# ConsoleSchematic.net
KiCad netlist of a schematic drawn in EAGLE
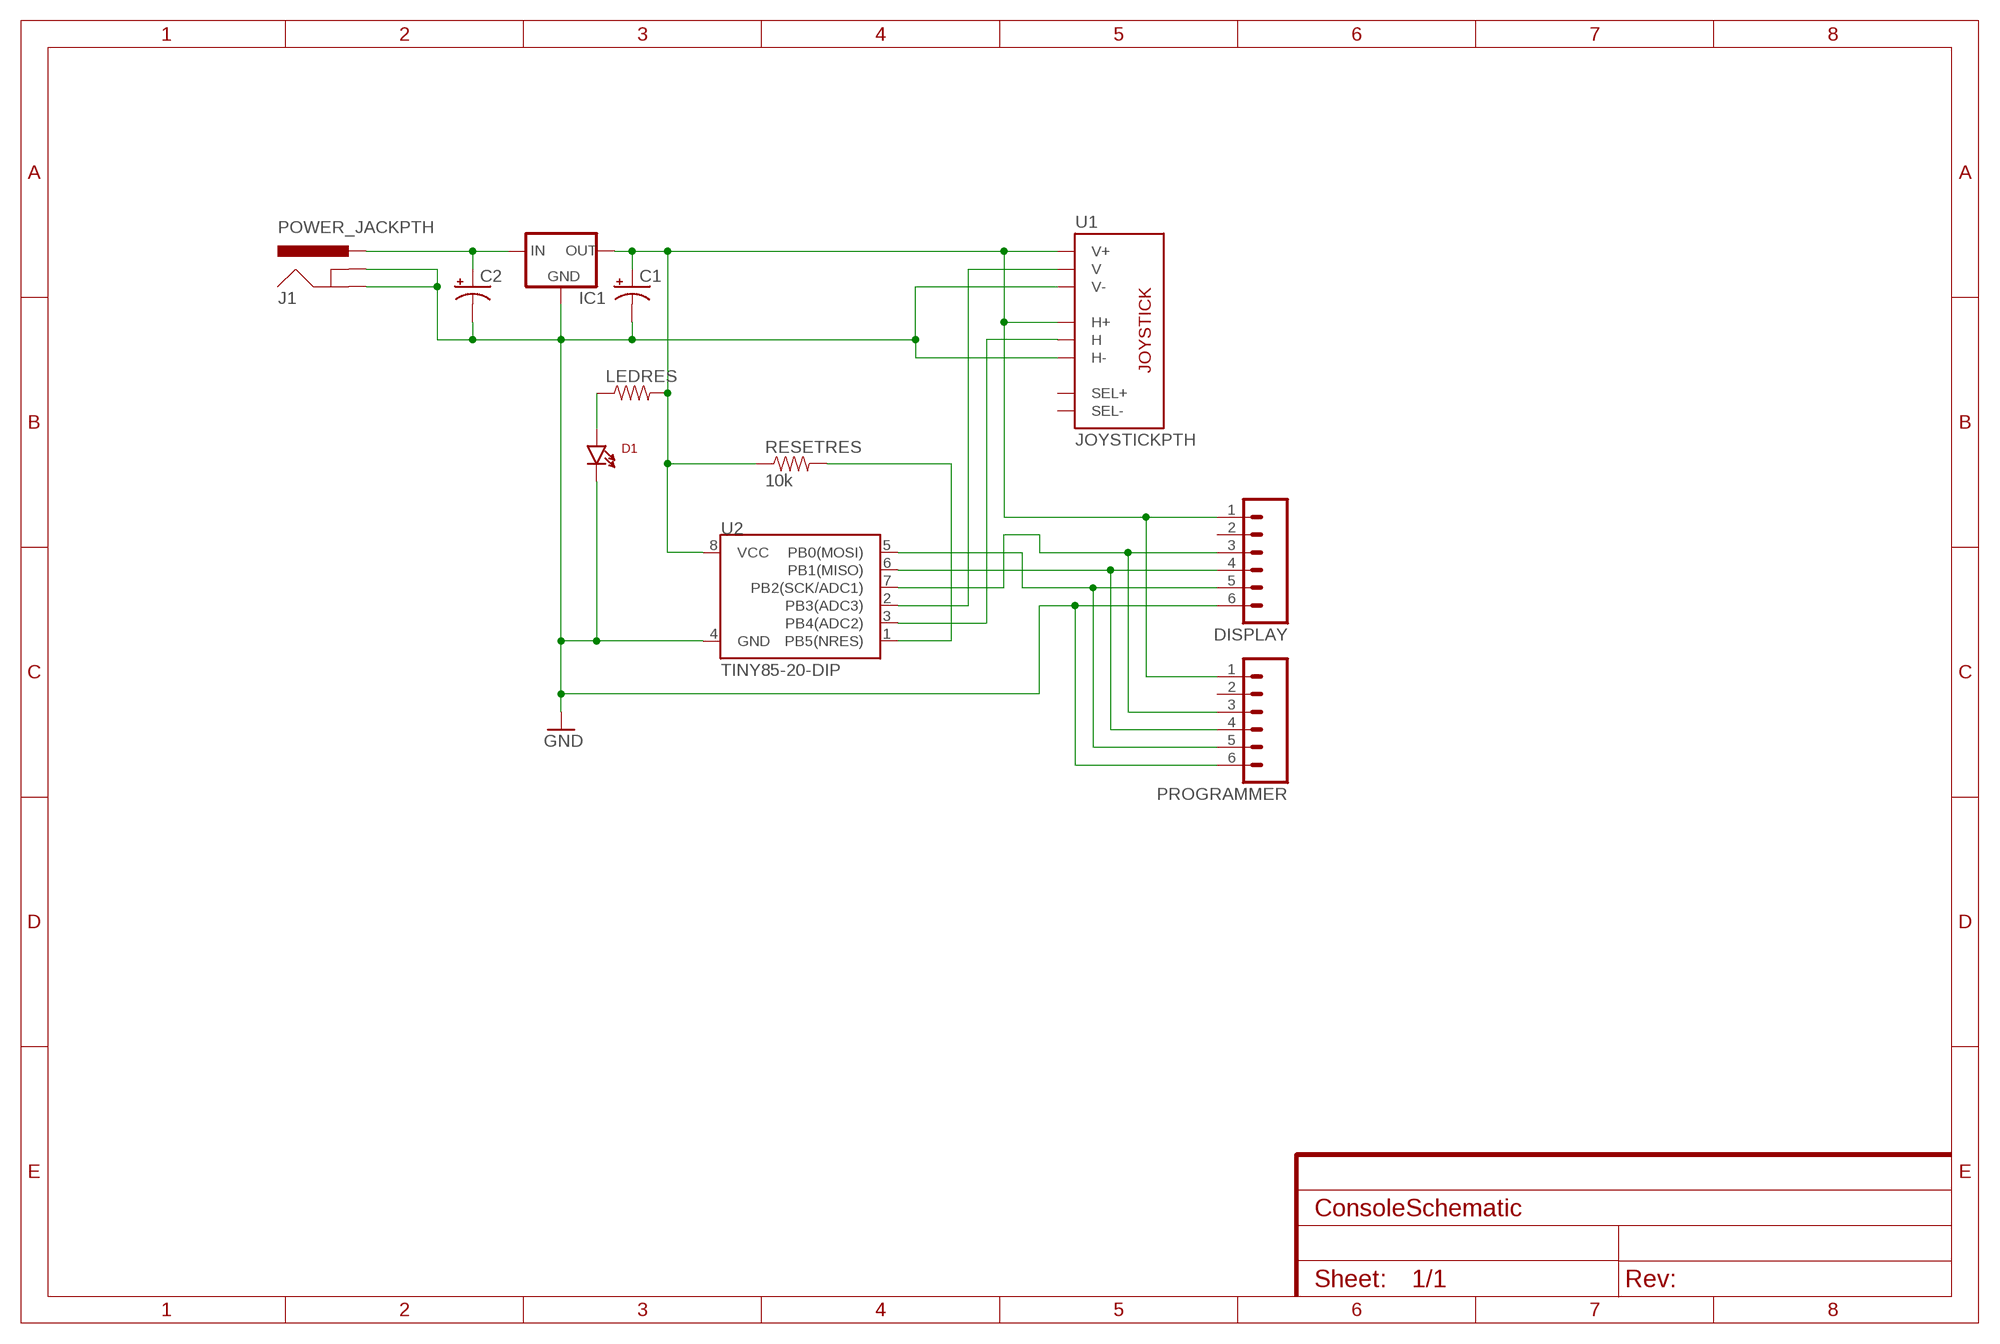
[diagram p0: schematic, sheet 1]

(export (version "E")
  (design (tool "Eeschema 10.0.6"))
  (components
    (comp (ref "C1")
      (value "10UF-25V-20%(PTH)KIT")
      (footprint "eagle-import:CPOL-RADIAL-10UF-25V-KIT")
      (libsource (lib "eagle-import") (part "10UF-25V-20%(PTH)KIT"))
    )
    (comp (ref "C2")
      (value "10UF-25V-20%(PTH)KIT")
      (footprint "eagle-import:CPOL-RADIAL-10UF-25V-KIT")
      (libsource (lib "eagle-import") (part "10UF-25V-20%(PTH)KIT"))
    )
    (comp (ref "D1")
      (value "LTE-302")
      (footprint "eagle-import:LTE-302")
      (libsource (lib "eagle-import") (part "LTE-302"))
    )
    (comp (ref "DISPLAY")
      (value "M06SILK_FEMALE_PTH")
      (footprint "eagle-import:1X06")
      (libsource (lib "eagle-import") (part "M06SILK_FEMALE_PTH"))
    )
    (comp (ref "IC1")
      (value "V_REG_78XXSIDE")
      (footprint "eagle-import:78XXL")
      (libsource (lib "eagle-import") (part "V_REG_78XXSIDE"))
    )
    (comp (ref "J1")
      (value "POWER_JACKPTH")
      (footprint "eagle-import:POWER_JACK_PTH")
      (libsource (lib "eagle-import") (part "POWER_JACKPTH"))
    )
    (comp (ref "LEDRES")
      (value "RESISTOREZ")
      (footprint "eagle-import:AXIAL-0.3EZ")
      (libsource (lib "eagle-import") (part "RESISTOREZ"))
    )
    (comp (ref "PROGRAMMER")
      (value "M06SILK_FEMALE_PTH")
      (footprint "eagle-import:1X06")
      (libsource (lib "eagle-import") (part "M06SILK_FEMALE_PTH"))
    )
    (comp (ref "RESETRES")
      (value "10k")
      (footprint "eagle-import:AXIAL-0.3")
      (libsource (lib "eagle-import") (part "10KOHM-1/4W-1%(PTH)HORIZ"))
    )
    (comp (ref "U1")
      (value "JOYSTICKPTH")
      (footprint "eagle-import:JOYSTICK")
      (libsource (lib "eagle-import") (part "JOYSTICKPTH"))
    )
    (comp (ref "U2")
      (value "TINY85-20-DIP")
      (footprint "eagle-import:DIP08")
      (libsource (lib "eagle-import") (part "ATTINY45TINY85-20-DIP"))
    )
  )
  (nets
    (net (code "1") (name "GND") (class "Default")
      (node (ref "C1") (pin "2") (pinfunction "-_2") (pintype "passive"))
      (node (ref "C2") (pin "2") (pinfunction "-_2") (pintype "passive"))
      (node (ref "D1") (pin "C") (pinfunction "C_C") (pintype "bidirectional"))
      (node (ref "DISPLAY") (pin "6") (pinfunction "6_6") (pintype "passive"))
      (node (ref "IC1") (pin "GND") (pinfunction "GND_GND") (pintype "input"))
      (node (ref "J1") (pin "GND") (pinfunction "GND_GND") (pintype "bidirectional"))
      (node (ref "J1") (pin "GNDBREAK") (pinfunction "GNDBREAK_GNDBREAK") (pintype "bidirectional"))
      (node (ref "PROGRAMMER") (pin "6") (pinfunction "6_6") (pintype "passive"))
      (node (ref "U1") (pin "H3") (pinfunction "H-_H3") (pintype "bidirectional"))
      (node (ref "U1") (pin "V3") (pinfunction "V-_V3") (pintype "bidirectional"))
      (node (ref "U2") (pin "4") (pinfunction "GND_4") (pintype "bidirectional"))
    )
    (net (code "2") (name "Net-(C1-+)") (class "Default")
      (node (ref "C1") (pin "1") (pinfunction "+_1") (pintype "passive"))
      (node (ref "DISPLAY") (pin "1") (pinfunction "1_1") (pintype "passive"))
      (node (ref "IC1") (pin "OUT") (pinfunction "OUT_OUT") (pintype "output"))
      (node (ref "LEDRES") (pin "P$2") (pinfunction "2_P$2") (pintype "passive"))
      (node (ref "PROGRAMMER") (pin "1") (pinfunction "1_1") (pintype "passive"))
      (node (ref "RESETRES") (pin "P$1") (pinfunction "1_P$1") (pintype "passive"))
      (node (ref "U1") (pin "H1") (pinfunction "H+_H1") (pintype "bidirectional"))
      (node (ref "U1") (pin "V1") (pinfunction "V+_V1") (pintype "bidirectional"))
      (node (ref "U2") (pin "8") (pinfunction "VCC_8") (pintype "bidirectional"))
    )
    (net (code "3") (name "Net-(C2-+)") (class "Default")
      (node (ref "C2") (pin "1") (pinfunction "+_1") (pintype "passive"))
      (node (ref "IC1") (pin "IN") (pinfunction "IN_IN") (pintype "input"))
      (node (ref "J1") (pin "PWR") (pinfunction "PWR_PWR") (pintype "bidirectional"))
    )
    (net (code "4") (name "Net-(LEDRES-1)") (class "Default")
      (node (ref "D1") (pin "A") (pinfunction "A_A") (pintype "bidirectional"))
      (node (ref "LEDRES") (pin "P$1") (pinfunction "1_P$1") (pintype "passive"))
    )
    (net (code "5") (name "Net-(RESETRES-2)") (class "Default")
      (node (ref "RESETRES") (pin "P$2") (pinfunction "2_P$2") (pintype "passive"))
      (node (ref "U2") (pin "1") (pinfunction "PB5(NRES)_1") (pintype "bidirectional"))
    )
    (net (code "6") (name "Net-(U1-H)") (class "Default")
      (node (ref "U1") (pin "H2") (pinfunction "H_H2") (pintype "bidirectional"))
      (node (ref "U2") (pin "3") (pinfunction "PB4(ADC2)_3") (pintype "bidirectional"))
    )
    (net (code "7") (name "Net-(U1-V)") (class "Default")
      (node (ref "U1") (pin "V2") (pinfunction "V_V2") (pintype "bidirectional"))
      (node (ref "U2") (pin "2") (pinfunction "PB3(ADC3)_2") (pintype "bidirectional"))
    )
    (net (code "8") (name "Net-(U2-PB0(MOSI))") (class "Default")
      (node (ref "DISPLAY") (pin "5") (pinfunction "5_5") (pintype "passive"))
      (node (ref "PROGRAMMER") (pin "5") (pinfunction "5_5") (pintype "passive"))
      (node (ref "U2") (pin "5") (pinfunction "PB0(MOSI)_5") (pintype "bidirectional"))
    )
    (net (code "9") (name "Net-(U2-PB1(MISO))") (class "Default")
      (node (ref "DISPLAY") (pin "4") (pinfunction "4_4") (pintype "passive"))
      (node (ref "PROGRAMMER") (pin "4") (pinfunction "4_4") (pintype "passive"))
      (node (ref "U2") (pin "6") (pinfunction "PB1(MISO)_6") (pintype "bidirectional"))
    )
    (net (code "10") (name "Net-(U2-PB2(SCK{slash}ADC1))") (class "Default")
      (node (ref "DISPLAY") (pin "3") (pinfunction "3_3") (pintype "passive"))
      (node (ref "PROGRAMMER") (pin "3") (pinfunction "3_3") (pintype "passive"))
      (node (ref "U2") (pin "7") (pinfunction "PB2(SCK/ADC1)_7") (pintype "bidirectional"))
    )
    (net (code "11") (name "unconnected-(DISPLAY-Pad2)") (class "Default")
      (node (ref "DISPLAY") (pin "2") (pinfunction "2_2") (pintype "passive"))
    )
    (net (code "12") (name "unconnected-(PROGRAMMER-Pad2)") (class "Default")
      (node (ref "PROGRAMMER") (pin "2") (pinfunction "2_2") (pintype "passive"))
    )
    (net (code "13") (name "unconnected-(U1-SEL+-PadB1A)") (class "Default")
      (node (ref "U1") (pin "B1A") (pinfunction "SEL+_B1A") (pintype "bidirectional"))
    )
    (net (code "14") (name "unconnected-(U1-SEL--PadB2A)") (class "Default")
      (node (ref "U1") (pin "B2A") (pinfunction "SEL-_B2A") (pintype "bidirectional"))
    )
  )
)
